# ProDoc_Board1_Smaller_2026-06-28.net
KiCad netlist of a schematic drawn in EasyEDA Pro
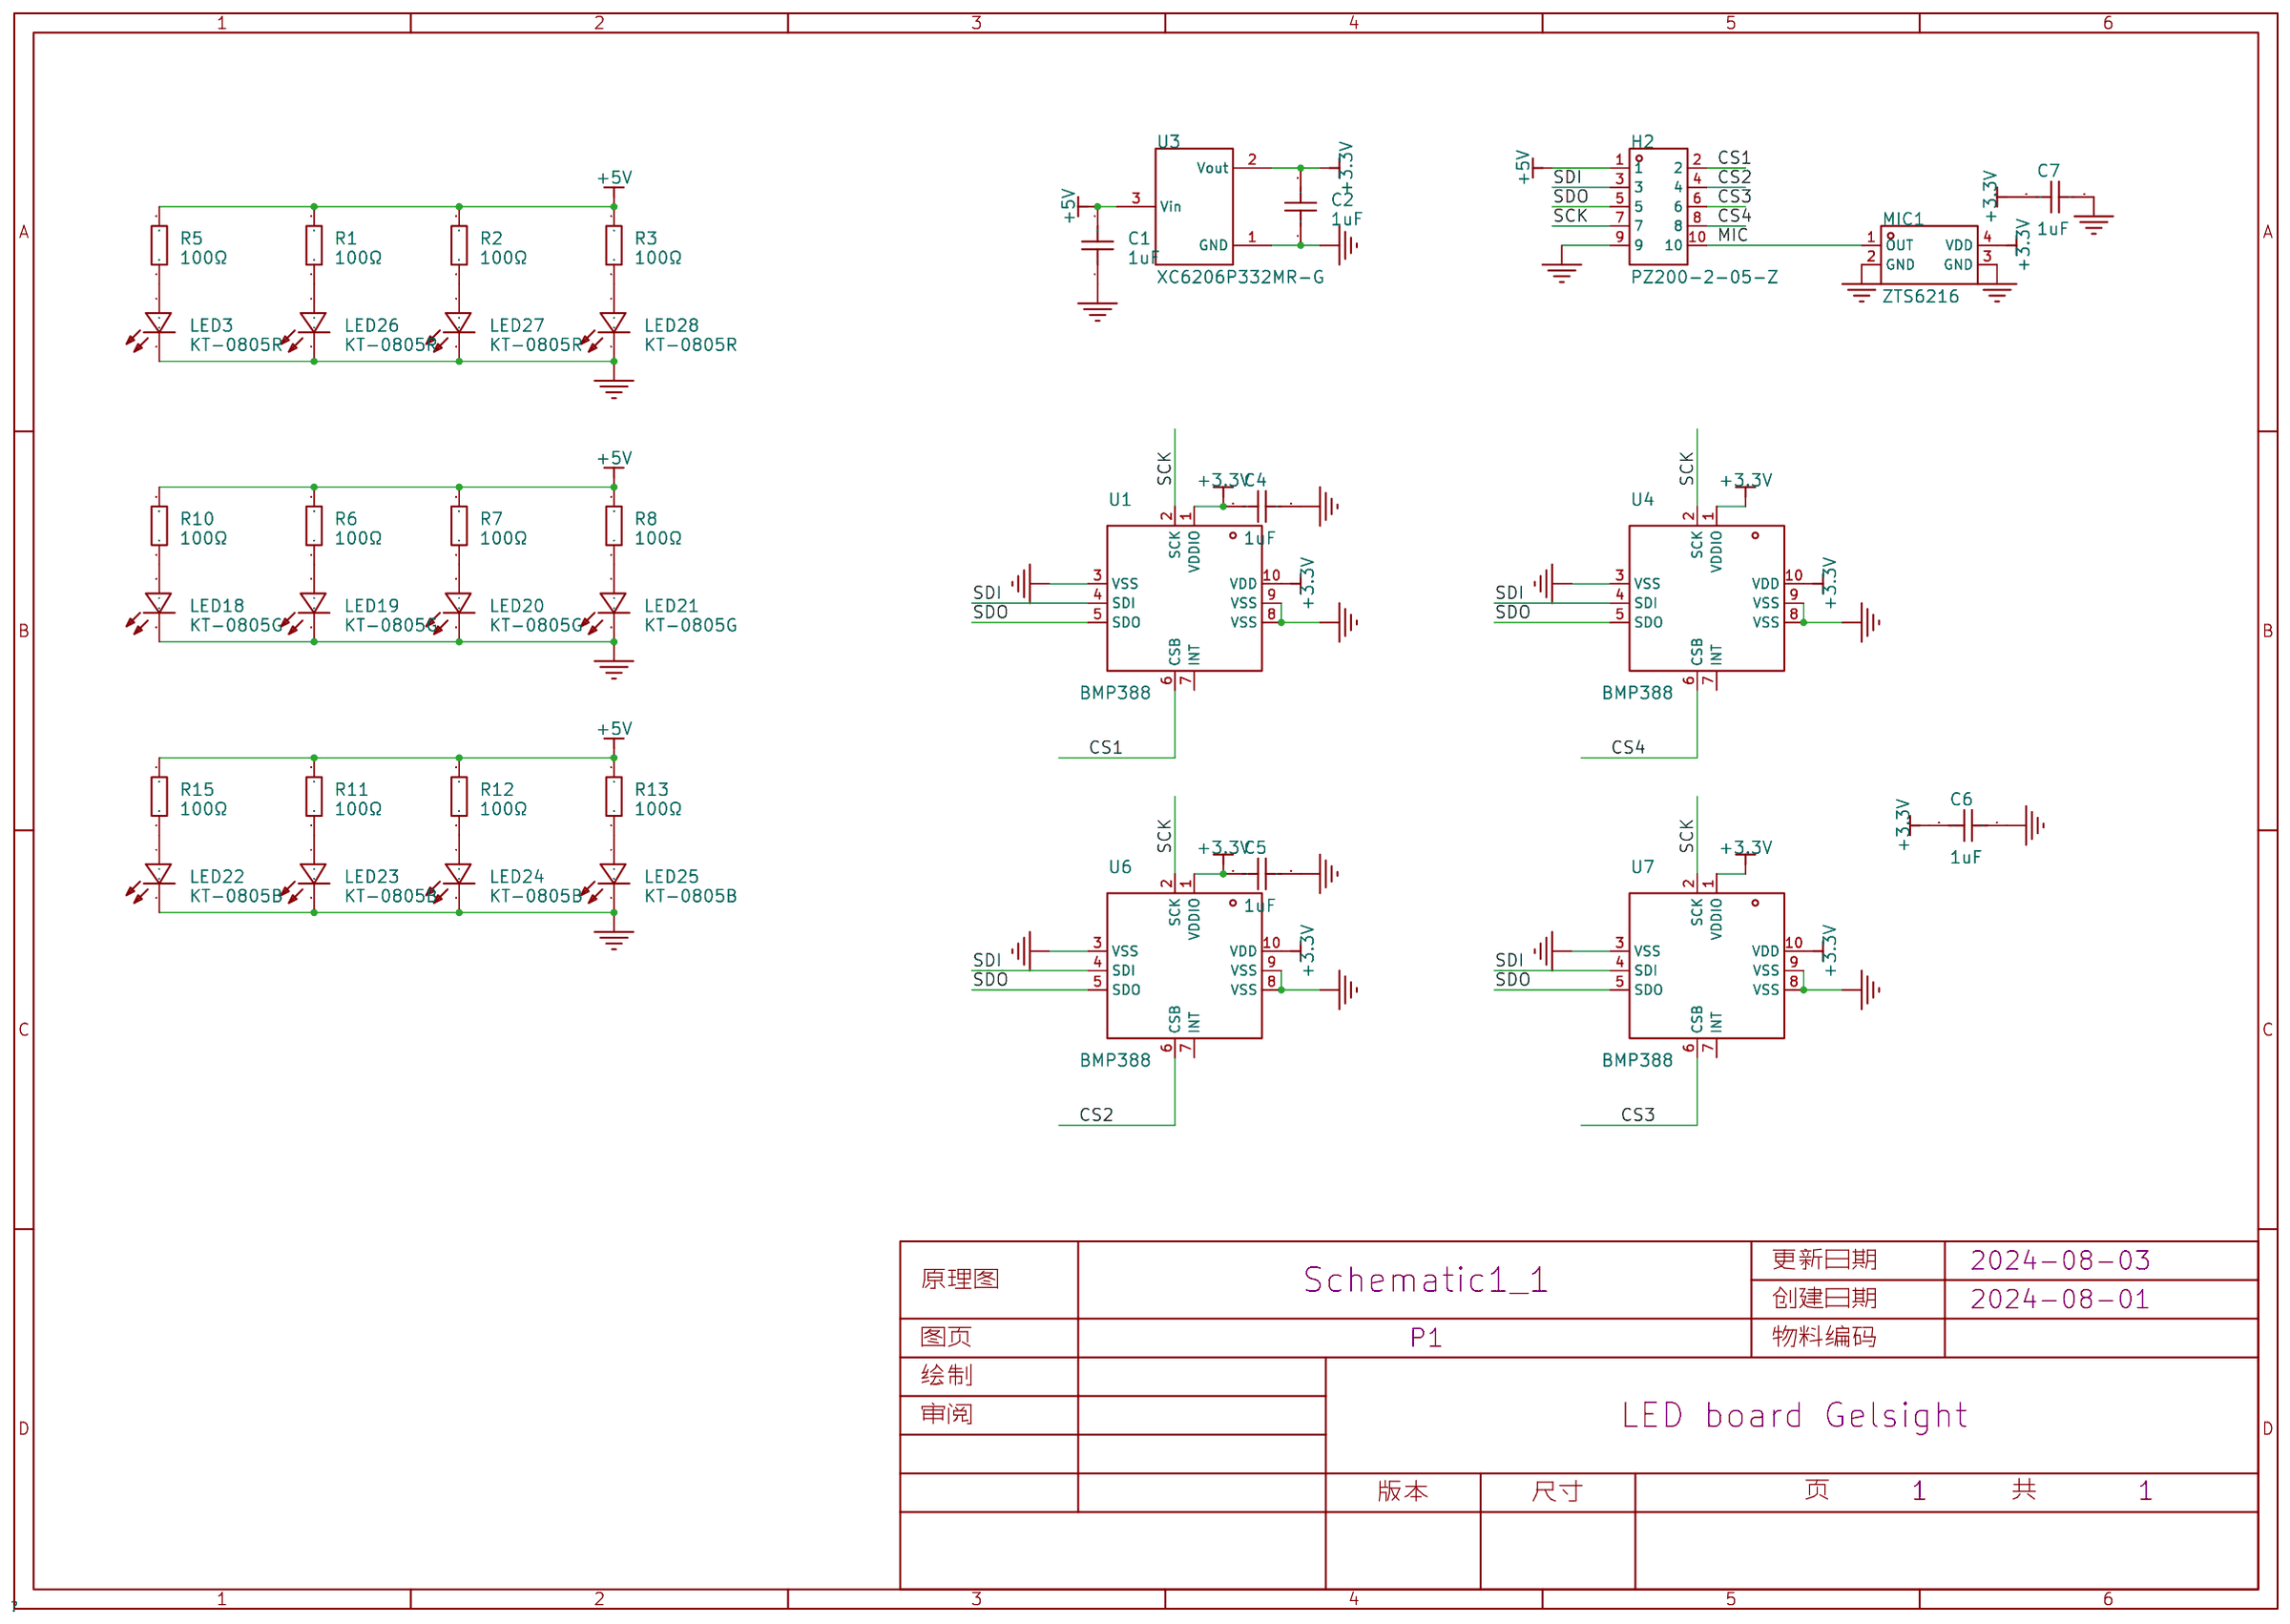
[diagram p0: schematic sheet]

(export (version "E")
  (design (tool "Eeschema 10.0.6"))
  (components
    (comp (ref "C1")
      (value "1uF")
      (footprint "easyedapro:C0402")
      (fields
        (field (name "Manufacturer Part") "CL05A105KA5NQNC")
        (field (name "Manufacturer") "SAMSUNG(三星)")
      )
      (libsource (lib "easyedapro") (part "CL05A105KA5NQNC"))
    )
    (comp (ref "C2")
      (value "1uF")
      (footprint "easyedapro:C0402")
      (fields
        (field (name "Manufacturer Part") "CL05A105KA5NQNC")
        (field (name "Manufacturer") "SAMSUNG(三星)")
      )
      (libsource (lib "easyedapro") (part "CL05A105KA5NQNC"))
    )
    (comp (ref "C4")
      (value "1uF")
      (footprint "easyedapro:C0402")
      (fields
        (field (name "Manufacturer Part") "CL05A105KA5NQNC")
        (field (name "Manufacturer") "SAMSUNG(三星)")
      )
      (libsource (lib "easyedapro") (part "CL05A105KA5NQNC"))
    )
    (comp (ref "C5")
      (value "1uF")
      (footprint "easyedapro:C0402")
      (fields
        (field (name "Manufacturer Part") "CL05A105KA5NQNC")
        (field (name "Manufacturer") "SAMSUNG(三星)")
      )
      (libsource (lib "easyedapro") (part "CL05A105KA5NQNC"))
    )
    (comp (ref "C6")
      (value "1uF")
      (footprint "easyedapro:C0402")
      (fields
        (field (name "Manufacturer Part") "CL05A105KA5NQNC")
        (field (name "Manufacturer") "SAMSUNG(三星)")
      )
      (libsource (lib "easyedapro") (part "CL05A105KA5NQNC"))
    )
    (comp (ref "C7")
      (value "1uF")
      (footprint "easyedapro:C0402")
      (fields
        (field (name "Manufacturer Part") "CL05A105KA5NQNC")
        (field (name "Manufacturer") "SAMSUNG(三星)")
      )
      (libsource (lib "easyedapro") (part "CL05A105KA5NQNC"))
    )
    (comp (ref "H2")
      (value "PZ200-2-05-Z")
      (footprint "easyedapro:HDR-TH_10P-P2.00-V-M-R2-C5-S2.00")
      (fields (field (name "Manufacturer") "HCTL(华灿天禄)"))
      (libsource (lib "easyedapro") (part "PZ200-2-05-Z"))
    )
    (comp (ref "LED3")
      (value "KT-0805R")
      (footprint "easyedapro:LED0805-R-RD")
      (fields (field (name "Manufacturer") "KENTO"))
      (libsource (lib "easyedapro") (part "E6C0805UR"))
    )
    (comp (ref "LED18")
      (value "KT-0805G")
      (footprint "easyedapro:LED0805-R-RD")
      (fields (field (name "Manufacturer") "KENTO"))
      (libsource (lib "easyedapro") (part "0805G (Green)"))
    )
    (comp (ref "LED19")
      (value "KT-0805G")
      (footprint "easyedapro:LED0805-R-RD")
      (fields (field (name "Manufacturer") "KENTO"))
      (libsource (lib "easyedapro") (part "0805G (Green)"))
    )
    (comp (ref "LED20")
      (value "KT-0805G")
      (footprint "easyedapro:LED0805-R-RD")
      (fields (field (name "Manufacturer") "KENTO"))
      (libsource (lib "easyedapro") (part "0805G (Green)"))
    )
    (comp (ref "LED21")
      (value "KT-0805G")
      (footprint "easyedapro:LED0805-R-RD")
      (fields (field (name "Manufacturer") "KENTO"))
      (libsource (lib "easyedapro") (part "0805G (Green)"))
    )
    (comp (ref "LED22")
      (value "KT-0805B")
      (footprint "easyedapro:LED0805-R-RD")
      (fields (field (name "Manufacturer") "KENTO"))
      (libsource (lib "easyedapro") (part "XL-0805QBC"))
    )
    (comp (ref "LED23")
      (value "KT-0805B")
      (footprint "easyedapro:LED0805-R-RD")
      (fields (field (name "Manufacturer") "KENTO"))
      (libsource (lib "easyedapro") (part "XL-0805QBC"))
    )
    (comp (ref "LED24")
      (value "KT-0805B")
      (footprint "easyedapro:LED0805-R-RD")
      (fields (field (name "Manufacturer") "KENTO"))
      (libsource (lib "easyedapro") (part "XL-0805QBC"))
    )
    (comp (ref "LED25")
      (value "KT-0805B")
      (footprint "easyedapro:LED0805-R-RD")
      (fields (field (name "Manufacturer") "KENTO"))
      (libsource (lib "easyedapro") (part "XL-0805QBC"))
    )
    (comp (ref "LED26")
      (value "KT-0805R")
      (footprint "easyedapro:LED0805-R-RD")
      (fields (field (name "Manufacturer") "KENTO"))
      (libsource (lib "easyedapro") (part "E6C0805UR"))
    )
    (comp (ref "LED27")
      (value "KT-0805R")
      (footprint "easyedapro:LED0805-R-RD")
      (fields (field (name "Manufacturer") "KENTO"))
      (libsource (lib "easyedapro") (part "E6C0805UR"))
    )
    (comp (ref "LED28")
      (value "KT-0805R")
      (footprint "easyedapro:LED0805-R-RD")
      (fields (field (name "Manufacturer") "KENTO"))
      (libsource (lib "easyedapro") (part "E6C0805UR"))
    )
    (comp (ref "MIC1")
      (value "ZTS6216")
      (footprint "easyedapro:MIC-SMD_4P-L2.8-W1.9-P1.84-TL")
      (fields (field (name "Manufacturer") "ZILLTEK(钰太)"))
      (libsource (lib "easyedapro") (part "ZTS6216"))
    )
    (comp (ref "R1")
      (value "100Ω")
      (footprint "easyedapro:R0402")
      (fields
        (field (name "Manufacturer Part") "0402WGF1000TCE")
        (field (name "Manufacturer") "UNI-ROYAL(厚声)")
      )
      (libsource (lib "easyedapro") (part "0402WGF1000TCE"))
    )
    (comp (ref "R2")
      (value "100Ω")
      (footprint "easyedapro:R0402")
      (fields
        (field (name "Manufacturer Part") "0402WGF1000TCE")
        (field (name "Manufacturer") "UNI-ROYAL(厚声)")
      )
      (libsource (lib "easyedapro") (part "0402WGF1000TCE"))
    )
    (comp (ref "R3")
      (value "100Ω")
      (footprint "easyedapro:R0402")
      (fields
        (field (name "Manufacturer Part") "0402WGF1000TCE")
        (field (name "Manufacturer") "UNI-ROYAL(厚声)")
      )
      (libsource (lib "easyedapro") (part "0402WGF1000TCE"))
    )
    (comp (ref "R5")
      (value "100Ω")
      (footprint "easyedapro:R0402")
      (fields
        (field (name "Manufacturer Part") "0402WGF1000TCE")
        (field (name "Manufacturer") "UNI-ROYAL(厚声)")
      )
      (libsource (lib "easyedapro") (part "0402WGF1000TCE"))
    )
    (comp (ref "R6")
      (value "100Ω")
      (footprint "easyedapro:R0402")
      (fields
        (field (name "Manufacturer Part") "0402WGF1000TCE")
        (field (name "Manufacturer") "UNI-ROYAL(厚声)")
      )
      (libsource (lib "easyedapro") (part "0402WGF1000TCE"))
    )
    (comp (ref "R7")
      (value "100Ω")
      (footprint "easyedapro:R0402")
      (fields
        (field (name "Manufacturer Part") "0402WGF1000TCE")
        (field (name "Manufacturer") "UNI-ROYAL(厚声)")
      )
      (libsource (lib "easyedapro") (part "0402WGF1000TCE"))
    )
    (comp (ref "R8")
      (value "100Ω")
      (footprint "easyedapro:R0402")
      (fields
        (field (name "Manufacturer Part") "0402WGF1000TCE")
        (field (name "Manufacturer") "UNI-ROYAL(厚声)")
      )
      (libsource (lib "easyedapro") (part "0402WGF1000TCE"))
    )
    (comp (ref "R10")
      (value "100Ω")
      (footprint "easyedapro:R0402")
      (fields
        (field (name "Manufacturer Part") "0402WGF1000TCE")
        (field (name "Manufacturer") "UNI-ROYAL(厚声)")
      )
      (libsource (lib "easyedapro") (part "0402WGF1000TCE"))
    )
    (comp (ref "R11")
      (value "100Ω")
      (footprint "easyedapro:R0402")
      (fields
        (field (name "Manufacturer Part") "0402WGF1000TCE")
        (field (name "Manufacturer") "UNI-ROYAL(厚声)")
      )
      (libsource (lib "easyedapro") (part "0402WGF1000TCE"))
    )
    (comp (ref "R12")
      (value "100Ω")
      (footprint "easyedapro:R0402")
      (fields
        (field (name "Manufacturer Part") "0402WGF1000TCE")
        (field (name "Manufacturer") "UNI-ROYAL(厚声)")
      )
      (libsource (lib "easyedapro") (part "0402WGF1000TCE"))
    )
    (comp (ref "R13")
      (value "100Ω")
      (footprint "easyedapro:R0402")
      (fields
        (field (name "Manufacturer Part") "0402WGF1000TCE")
        (field (name "Manufacturer") "UNI-ROYAL(厚声)")
      )
      (libsource (lib "easyedapro") (part "0402WGF1000TCE"))
    )
    (comp (ref "R15")
      (value "100Ω")
      (footprint "easyedapro:R0402")
      (fields
        (field (name "Manufacturer Part") "0402WGF1000TCE")
        (field (name "Manufacturer") "UNI-ROYAL(厚声)")
      )
      (libsource (lib "easyedapro") (part "0402WGF1000TCE"))
    )
    (comp (ref "U1")
      (value "BMP388")
      (footprint "easyedapro:SENSORM-SMD_BMP388")
      (fields (field (name "Manufacturer") "Bosch(博世)"))
      (libsource (lib "easyedapro") (part "BMP388"))
    )
    (comp (ref "U3")
      (value "XC6206P332MR-G")
      (footprint "easyedapro:SOT-23-3_L2.9-W1.6-P1.90-LS2.8-BR")
      (fields (field (name "Manufacturer") "TOREX(特瑞仕)"))
      (libsource (lib "easyedapro") (part "XC6206P332MR"))
    )
    (comp (ref "U4")
      (value "BMP388")
      (footprint "easyedapro:SENSORM-SMD_BMP388")
      (fields (field (name "Manufacturer") "Bosch(博世)"))
      (libsource (lib "easyedapro") (part "BMP388"))
    )
    (comp (ref "U6")
      (value "BMP388")
      (footprint "easyedapro:SENSORM-SMD_BMP388")
      (fields (field (name "Manufacturer") "Bosch(博世)"))
      (libsource (lib "easyedapro") (part "BMP388"))
    )
    (comp (ref "U7")
      (value "BMP388")
      (footprint "easyedapro:SENSORM-SMD_BMP388")
      (fields (field (name "Manufacturer") "Bosch(博世)"))
      (libsource (lib "easyedapro") (part "BMP388"))
    )
  )
  (nets
    (net (code "1") (name "+3.3V") (class "Default")
      (node (ref "C2") (pin "2") (pinfunction "2_2") (pintype "unspecified"))
      (node (ref "C4") (pin "2") (pinfunction "2_2") (pintype "unspecified"))
      (node (ref "C5") (pin "2") (pinfunction "2_2") (pintype "unspecified"))
      (node (ref "C6") (pin "2") (pinfunction "2_2") (pintype "unspecified"))
      (node (ref "C7") (pin "1") (pinfunction "1_1") (pintype "unspecified"))
      (node (ref "MIC1") (pin "4") (pinfunction "VDD_4") (pintype "input"))
      (node (ref "U1") (pin "1") (pinfunction "VDDIO_1") (pintype "unspecified"))
      (node (ref "U1") (pin "10") (pinfunction "VDD_10") (pintype "unspecified"))
      (node (ref "U3") (pin "2") (pinfunction "Vout_2") (pintype "unspecified"))
      (node (ref "U4") (pin "1") (pinfunction "VDDIO_1") (pintype "unspecified"))
      (node (ref "U4") (pin "10") (pinfunction "VDD_10") (pintype "unspecified"))
      (node (ref "U6") (pin "1") (pinfunction "VDDIO_1") (pintype "unspecified"))
      (node (ref "U6") (pin "10") (pinfunction "VDD_10") (pintype "unspecified"))
      (node (ref "U7") (pin "1") (pinfunction "VDDIO_1") (pintype "unspecified"))
      (node (ref "U7") (pin "10") (pinfunction "VDD_10") (pintype "unspecified"))
    )
    (net (code "2") (name "+5V") (class "Default")
      (node (ref "C1") (pin "2") (pinfunction "2_2") (pintype "unspecified"))
      (node (ref "H2") (pin "1") (pinfunction "1_1") (pintype "unspecified"))
      (node (ref "R1") (pin "2") (pinfunction "2_2") (pintype "input"))
      (node (ref "R10") (pin "2") (pinfunction "2_2") (pintype "input"))
      (node (ref "R11") (pin "2") (pinfunction "2_2") (pintype "input"))
      (node (ref "R12") (pin "2") (pinfunction "2_2") (pintype "input"))
      (node (ref "R13") (pin "2") (pinfunction "2_2") (pintype "input"))
      (node (ref "R15") (pin "2") (pinfunction "2_2") (pintype "input"))
      (node (ref "R2") (pin "2") (pinfunction "2_2") (pintype "input"))
      (node (ref "R3") (pin "2") (pinfunction "2_2") (pintype "input"))
      (node (ref "R5") (pin "2") (pinfunction "2_2") (pintype "input"))
      (node (ref "R6") (pin "2") (pinfunction "2_2") (pintype "input"))
      (node (ref "R7") (pin "2") (pinfunction "2_2") (pintype "input"))
      (node (ref "R8") (pin "2") (pinfunction "2_2") (pintype "input"))
      (node (ref "U3") (pin "3") (pinfunction "Vin_3") (pintype "unspecified"))
    )
    (net (code "3") (name "/CS1") (class "Default")
      (node (ref "H2") (pin "2") (pinfunction "2_2") (pintype "unspecified"))
      (node (ref "U1") (pin "6") (pinfunction "CSB_6") (pintype "unspecified"))
    )
    (net (code "4") (name "/CS2") (class "Default")
      (node (ref "H2") (pin "4") (pinfunction "4_4") (pintype "unspecified"))
      (node (ref "U6") (pin "6") (pinfunction "CSB_6") (pintype "unspecified"))
    )
    (net (code "5") (name "/CS3") (class "Default")
      (node (ref "H2") (pin "6") (pinfunction "6_6") (pintype "unspecified"))
      (node (ref "U7") (pin "6") (pinfunction "CSB_6") (pintype "unspecified"))
    )
    (net (code "6") (name "/CS4") (class "Default")
      (node (ref "H2") (pin "8") (pinfunction "8_8") (pintype "unspecified"))
      (node (ref "U4") (pin "6") (pinfunction "CSB_6") (pintype "unspecified"))
    )
    (net (code "7") (name "/MIC") (class "Default")
      (node (ref "H2") (pin "10") (pinfunction "10_10") (pintype "unspecified"))
      (node (ref "MIC1") (pin "1") (pinfunction "OUT_1") (pintype "input"))
    )
    (net (code "8") (name "/SCK") (class "Default")
      (node (ref "H2") (pin "7") (pinfunction "7_7") (pintype "unspecified"))
      (node (ref "U1") (pin "2") (pinfunction "SCK_2") (pintype "unspecified"))
      (node (ref "U4") (pin "2") (pinfunction "SCK_2") (pintype "unspecified"))
      (node (ref "U6") (pin "2") (pinfunction "SCK_2") (pintype "unspecified"))
      (node (ref "U7") (pin "2") (pinfunction "SCK_2") (pintype "unspecified"))
    )
    (net (code "9") (name "/SDI") (class "Default")
      (node (ref "H2") (pin "3") (pinfunction "3_3") (pintype "unspecified"))
      (node (ref "U1") (pin "4") (pinfunction "SDI_4") (pintype "unspecified"))
      (node (ref "U4") (pin "4") (pinfunction "SDI_4") (pintype "unspecified"))
      (node (ref "U6") (pin "4") (pinfunction "SDI_4") (pintype "unspecified"))
      (node (ref "U7") (pin "4") (pinfunction "SDI_4") (pintype "unspecified"))
    )
    (net (code "10") (name "/SDO") (class "Default")
      (node (ref "H2") (pin "5") (pinfunction "5_5") (pintype "unspecified"))
      (node (ref "U1") (pin "5") (pinfunction "SDO_5") (pintype "unspecified"))
      (node (ref "U4") (pin "5") (pinfunction "SDO_5") (pintype "unspecified"))
      (node (ref "U6") (pin "5") (pinfunction "SDO_5") (pintype "unspecified"))
      (node (ref "U7") (pin "5") (pinfunction "SDO_5") (pintype "unspecified"))
    )
    (net (code "11") (name "GND") (class "Default")
      (node (ref "C1") (pin "1") (pinfunction "1_1") (pintype "unspecified"))
      (node (ref "C2") (pin "1") (pinfunction "1_1") (pintype "unspecified"))
      (node (ref "C4") (pin "1") (pinfunction "1_1") (pintype "unspecified"))
      (node (ref "C5") (pin "1") (pinfunction "1_1") (pintype "unspecified"))
      (node (ref "C6") (pin "1") (pinfunction "1_1") (pintype "unspecified"))
      (node (ref "C7") (pin "2") (pinfunction "2_2") (pintype "unspecified"))
      (node (ref "H2") (pin "9") (pinfunction "9_9") (pintype "unspecified"))
      (node (ref "LED18") (pin "2") (pinfunction "K_2") (pintype "unspecified"))
      (node (ref "LED19") (pin "2") (pinfunction "K_2") (pintype "unspecified"))
      (node (ref "LED20") (pin "2") (pinfunction "K_2") (pintype "unspecified"))
      (node (ref "LED21") (pin "2") (pinfunction "K_2") (pintype "unspecified"))
      (node (ref "LED22") (pin "2") (pinfunction "K_2") (pintype "unspecified"))
      (node (ref "LED23") (pin "2") (pinfunction "K_2") (pintype "unspecified"))
      (node (ref "LED24") (pin "2") (pinfunction "K_2") (pintype "unspecified"))
      (node (ref "LED25") (pin "2") (pinfunction "K_2") (pintype "unspecified"))
      (node (ref "LED26") (pin "2") (pinfunction "K_2") (pintype "unspecified"))
      (node (ref "LED27") (pin "2") (pinfunction "K_2") (pintype "unspecified"))
      (node (ref "LED28") (pin "2") (pinfunction "K_2") (pintype "unspecified"))
      (node (ref "LED3") (pin "2") (pinfunction "K_2") (pintype "unspecified"))
      (node (ref "MIC1") (pin "2") (pinfunction "GND_2") (pintype "input"))
      (node (ref "MIC1") (pin "3") (pinfunction "GND_3") (pintype "input"))
      (node (ref "U1") (pin "3") (pinfunction "VSS_3") (pintype "unspecified"))
      (node (ref "U1") (pin "8") (pinfunction "VSS_8") (pintype "unspecified"))
      (node (ref "U1") (pin "9") (pinfunction "VSS_9") (pintype "unspecified"))
      (node (ref "U3") (pin "1") (pinfunction "GND_1") (pintype "unspecified"))
      (node (ref "U4") (pin "3") (pinfunction "VSS_3") (pintype "unspecified"))
      (node (ref "U4") (pin "8") (pinfunction "VSS_8") (pintype "unspecified"))
      (node (ref "U4") (pin "9") (pinfunction "VSS_9") (pintype "unspecified"))
      (node (ref "U6") (pin "3") (pinfunction "VSS_3") (pintype "unspecified"))
      (node (ref "U6") (pin "8") (pinfunction "VSS_8") (pintype "unspecified"))
      (node (ref "U6") (pin "9") (pinfunction "VSS_9") (pintype "unspecified"))
      (node (ref "U7") (pin "3") (pinfunction "VSS_3") (pintype "unspecified"))
      (node (ref "U7") (pin "8") (pinfunction "VSS_8") (pintype "unspecified"))
      (node (ref "U7") (pin "9") (pinfunction "VSS_9") (pintype "unspecified"))
    )
    (net (code "12") (name "Net-(LED3-A)") (class "Default")
      (node (ref "LED3") (pin "1") (pinfunction "A_1") (pintype "unspecified"))
      (node (ref "R5") (pin "1") (pinfunction "1_1") (pintype "input"))
    )
    (net (code "13") (name "Net-(LED18-A)") (class "Default")
      (node (ref "LED18") (pin "1") (pinfunction "A_1") (pintype "unspecified"))
      (node (ref "R10") (pin "1") (pinfunction "1_1") (pintype "input"))
    )
    (net (code "14") (name "Net-(LED19-A)") (class "Default")
      (node (ref "LED19") (pin "1") (pinfunction "A_1") (pintype "unspecified"))
      (node (ref "R6") (pin "1") (pinfunction "1_1") (pintype "input"))
    )
    (net (code "15") (name "Net-(LED20-A)") (class "Default")
      (node (ref "LED20") (pin "1") (pinfunction "A_1") (pintype "unspecified"))
      (node (ref "R7") (pin "1") (pinfunction "1_1") (pintype "input"))
    )
    (net (code "16") (name "Net-(LED21-A)") (class "Default")
      (node (ref "LED21") (pin "1") (pinfunction "A_1") (pintype "unspecified"))
      (node (ref "R8") (pin "1") (pinfunction "1_1") (pintype "input"))
    )
    (net (code "17") (name "Net-(LED22-A)") (class "Default")
      (node (ref "LED22") (pin "1") (pinfunction "A_1") (pintype "unspecified"))
      (node (ref "R15") (pin "1") (pinfunction "1_1") (pintype "input"))
    )
    (net (code "18") (name "Net-(LED23-A)") (class "Default")
      (node (ref "LED23") (pin "1") (pinfunction "A_1") (pintype "unspecified"))
      (node (ref "R11") (pin "1") (pinfunction "1_1") (pintype "input"))
    )
    (net (code "19") (name "Net-(LED24-A)") (class "Default")
      (node (ref "LED24") (pin "1") (pinfunction "A_1") (pintype "unspecified"))
      (node (ref "R12") (pin "1") (pinfunction "1_1") (pintype "input"))
    )
    (net (code "20") (name "Net-(LED25-A)") (class "Default")
      (node (ref "LED25") (pin "1") (pinfunction "A_1") (pintype "unspecified"))
      (node (ref "R13") (pin "1") (pinfunction "1_1") (pintype "input"))
    )
    (net (code "21") (name "Net-(LED26-A)") (class "Default")
      (node (ref "LED26") (pin "1") (pinfunction "A_1") (pintype "unspecified"))
      (node (ref "R1") (pin "1") (pinfunction "1_1") (pintype "input"))
    )
    (net (code "22") (name "Net-(LED27-A)") (class "Default")
      (node (ref "LED27") (pin "1") (pinfunction "A_1") (pintype "unspecified"))
      (node (ref "R2") (pin "1") (pinfunction "1_1") (pintype "input"))
    )
    (net (code "23") (name "Net-(LED28-A)") (class "Default")
      (node (ref "LED28") (pin "1") (pinfunction "A_1") (pintype "unspecified"))
      (node (ref "R3") (pin "1") (pinfunction "1_1") (pintype "input"))
    )
    (net (code "24") (name "unconnected-(U1-INT-Pad7)") (class "Default")
      (node (ref "U1") (pin "7") (pinfunction "INT_7") (pintype "unspecified"))
    )
    (net (code "25") (name "unconnected-(U4-INT-Pad7)") (class "Default")
      (node (ref "U4") (pin "7") (pinfunction "INT_7") (pintype "unspecified"))
    )
    (net (code "26") (name "unconnected-(U6-INT-Pad7)") (class "Default")
      (node (ref "U6") (pin "7") (pinfunction "INT_7") (pintype "unspecified"))
    )
    (net (code "27") (name "unconnected-(U7-INT-Pad7)") (class "Default")
      (node (ref "U7") (pin "7") (pinfunction "INT_7") (pintype "unspecified"))
    )
  )
)
